# oresat-zpos-endcap.net
KiCad netlist of a schematic drawn in EAGLE
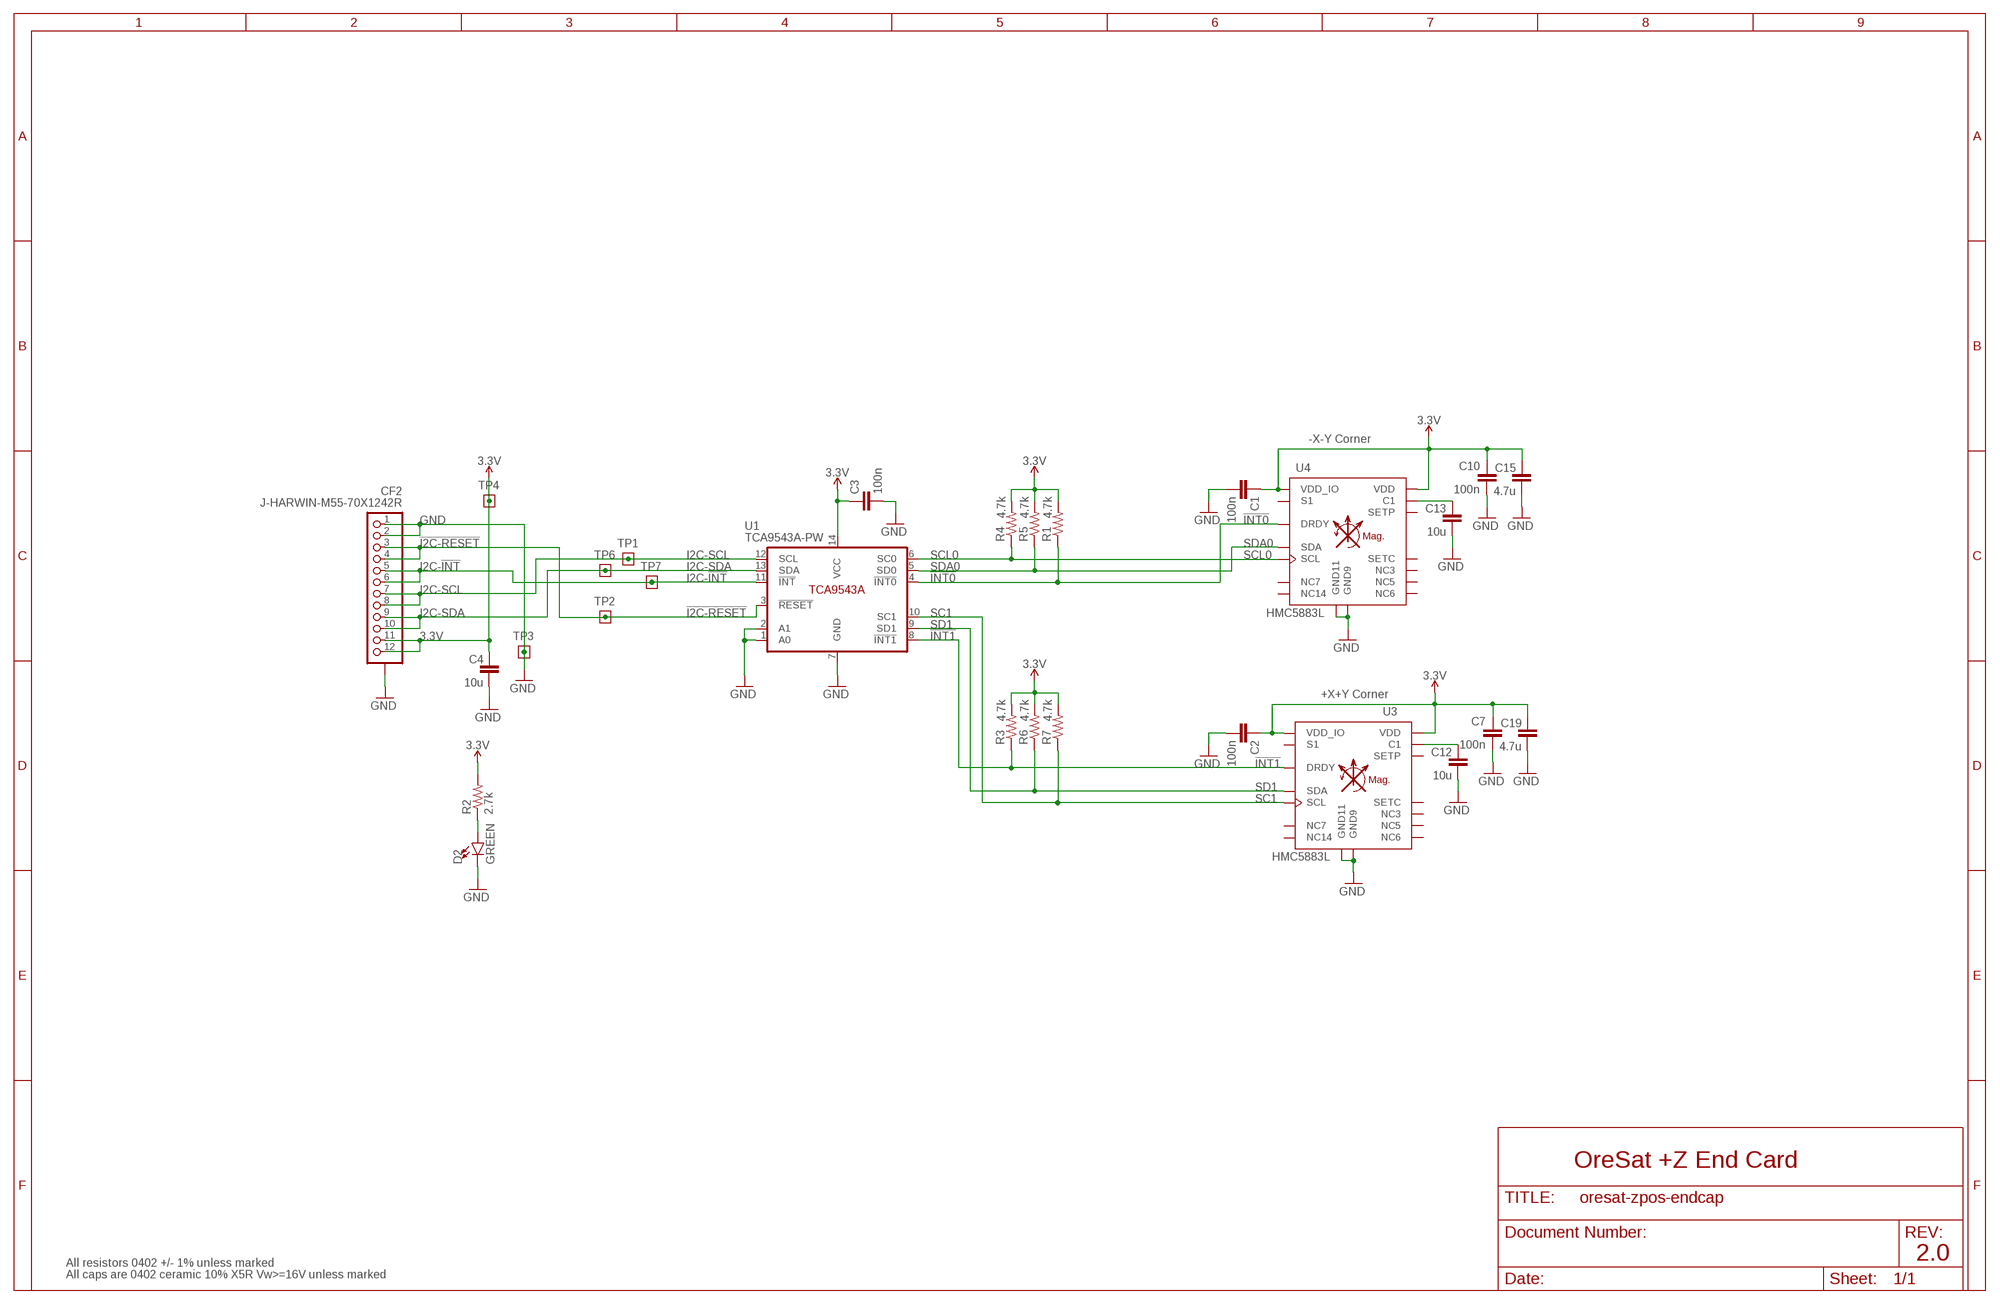
[diagram p0: schematic, sheet 1]

(export (version "E")
  (design (tool "Eeschema 10.0.6"))
  (components
    (comp (ref "C1")
      (value "100n")
      (footprint "eagle-import:.0402-B-NOSILK")
      (fields (field (name "MFR") "Samsung") (field (name "MPN") "CL05B104KO5NNNC"))
      (libsource (lib "eagle-import") (part "rcl_custom_C-EU0402-B-NOSILK"))
    )
    (comp (ref "C2")
      (value "100n")
      (footprint "eagle-import:.0402-B-NOSILK")
      (fields (field (name "MFR") "Samsung") (field (name "MPN") "CL05B104KO5NNNC"))
      (libsource (lib "eagle-import") (part "rcl_custom_C-EU0402-B-NOSILK"))
    )
    (comp (ref "C3")
      (value "100n")
      (footprint "eagle-import:.0402-B-NOSILK")
      (fields (field (name "MFR") "Samsung") (field (name "MPN") "CL05B104KO5NNNC"))
      (libsource (lib "eagle-import") (part "rcl_custom_C-EU0402-B-NOSILK"))
    )
    (comp (ref "C4")
      (value "10u")
      (footprint "eagle-import:.0603-B-NOSILK")
      (fields (field (name "MFR") "Samsung") (field (name "MPN") "CL05B104KO5NNNC"))
      (libsource (lib "eagle-import") (part "C-EU0603-B-NOSILK"))
    )
    (comp (ref "C7")
      (value "100n")
      (footprint "eagle-import:.0402-B-NOSILK")
      (fields (field (name "MFR") "Samsung") (field (name "MPN") "CL05B104KO5NNNC"))
      (libsource (lib "eagle-import") (part "rcl_custom_C-EU0402-B-NOSILK"))
    )
    (comp (ref "C10")
      (value "100n")
      (footprint "eagle-import:.0402-B-NOSILK")
      (fields (field (name "MFR") "Samsung") (field (name "MPN") "CL05B104KO5NNNC"))
      (libsource (lib "eagle-import") (part "rcl_custom_C-EU0402-B-NOSILK"))
    )
    (comp (ref "C12")
      (value "10u")
      (footprint "eagle-import:.0603-B-NOSILK")
      (fields (field (name "MFR") "Samsung") (field (name "MPN") "CL05B104KO5NNNC"))
      (libsource (lib "eagle-import") (part "C-EU0603-B-NOSILK"))
    )
    (comp (ref "C13")
      (value "10u")
      (footprint "eagle-import:.0603-B-NOSILK")
      (fields (field (name "MFR") "Samsung") (field (name "MPN") "CL05B104KO5NNNC"))
      (libsource (lib "eagle-import") (part "C-EU0603-B-NOSILK"))
    )
    (comp (ref "C15")
      (value "4.7u")
      (footprint "eagle-import:.0603-B-NOSILK")
      (fields (field (name "MFR") "Samsung") (field (name "MPN") "CL05B104KO5NNNC"))
      (libsource (lib "eagle-import") (part "C-EU0603-B-NOSILK"))
    )
    (comp (ref "C19")
      (value "4.7u")
      (footprint "eagle-import:.0603-B-NOSILK")
      (fields (field (name "MFR") "Samsung") (field (name "MPN") "CL05B104KO5NNNC"))
      (libsource (lib "eagle-import") (part "C-EU0603-B-NOSILK"))
    )
    (comp (ref "CF2")
      (value "J-HARWIN-M55-70X1242R")
      (footprint "eagle-import:HARWIN-M55-70X1242R")
      (libsource (lib "eagle-import") (part "J-HARWIN-M55-70X1242R"))
    )
    (comp (ref "D2")
      (value "GREEN")
      (footprint "eagle-import:LED-0603")
      (libsource (lib "eagle-import") (part "LED-GREEN0603"))
    )
    (comp (ref "R1")
      (value "4.7k")
      (footprint "eagle-import:.0402-B-NOSILK")
      (fields (field (name "MFR") "Samsung") (field (name "MPN") "RC1005F6653CS"))
      (libsource (lib "eagle-import") (part "R-US_0402-B-NOSILK"))
    )
    (comp (ref "R2")
      (value "2.7k")
      (footprint "eagle-import:.0402-B-NOSILK")
      (fields (field (name "MFR") "Samsung") (field (name "MPN") "RC1005F6653CS"))
      (libsource (lib "eagle-import") (part "R-US_0402-B-NOSILK"))
    )
    (comp (ref "R3")
      (value "4.7k")
      (footprint "eagle-import:.0402-B-NOSILK")
      (fields (field (name "MFR") "Samsung") (field (name "MPN") "RC1005F6653CS"))
      (libsource (lib "eagle-import") (part "R-US_0402-B-NOSILK"))
    )
    (comp (ref "R4")
      (value "4.7k")
      (footprint "eagle-import:.0402-B-NOSILK")
      (fields (field (name "MFR") "Samsung") (field (name "MPN") "RC1005F6653CS"))
      (libsource (lib "eagle-import") (part "R-US_0402-B-NOSILK"))
    )
    (comp (ref "R5")
      (value "4.7k")
      (footprint "eagle-import:.0402-B-NOSILK")
      (fields (field (name "MFR") "Samsung") (field (name "MPN") "RC1005F6653CS"))
      (libsource (lib "eagle-import") (part "R-US_0402-B-NOSILK"))
    )
    (comp (ref "R6")
      (value "4.7k")
      (footprint "eagle-import:.0402-B-NOSILK")
      (fields (field (name "MFR") "Samsung") (field (name "MPN") "RC1005F6653CS"))
      (libsource (lib "eagle-import") (part "R-US_0402-B-NOSILK"))
    )
    (comp (ref "R7")
      (value "4.7k")
      (footprint "eagle-import:.0402-B-NOSILK")
      (fields (field (name "MFR") "Samsung") (field (name "MPN") "RC1005F6653CS"))
      (libsource (lib "eagle-import") (part "R-US_0402-B-NOSILK"))
    )
    (comp (ref "TP1")
      (value "TEST-POINT")
      (footprint "eagle-import:2MM-TEST-POINT")
      (libsource (lib "eagle-import") (part "TEST-POINT"))
    )
    (comp (ref "TP2")
      (value "TEST-POINT")
      (footprint "eagle-import:2MM-TEST-POINT")
      (libsource (lib "eagle-import") (part "TEST-POINT"))
    )
    (comp (ref "TP3")
      (value "TEST-POINT")
      (footprint "eagle-import:2MM-TEST-POINT")
      (libsource (lib "eagle-import") (part "TEST-POINT"))
    )
    (comp (ref "TP4")
      (value "TEST-POINT")
      (footprint "eagle-import:2MM-TEST-POINT")
      (libsource (lib "eagle-import") (part "TEST-POINT"))
    )
    (comp (ref "TP6")
      (value "TEST-POINT")
      (footprint "eagle-import:2MM-TEST-POINT")
      (libsource (lib "eagle-import") (part "TEST-POINT"))
    )
    (comp (ref "TP7")
      (value "TEST-POINT")
      (footprint "eagle-import:2MM-TEST-POINT")
      (libsource (lib "eagle-import") (part "TEST-POINT"))
    )
    (comp (ref "U1")
      (value "TCA9543A-PW")
      (footprint "eagle-import:TSSOP14-0.65-5.4X4.4MM")
      (libsource (lib "eagle-import") (part "TCA9543A-PW"))
    )
    (comp (ref "U3")
      (value "HMC5883L")
      (footprint "eagle-import:QLGA-16(3X3)")
      (libsource (lib "eagle-import") (part "HMC5883L-LGA-16"))
    )
    (comp (ref "U4")
      (value "HMC5883L")
      (footprint "eagle-import:QLGA-16(3X3)")
      (libsource (lib "eagle-import") (part "HMC5883L-LGA-16"))
    )
  )
  (nets
    (net (code "1") (name "/I2C-SCL") (class "Default")
      (node (ref "CF2") (pin "7") (pinfunction "7_7") (pintype "passive"))
      (node (ref "CF2") (pin "8") (pinfunction "8_8") (pintype "passive"))
      (node (ref "TP1") (pin "1") (pinfunction "1_1") (pintype "passive"))
      (node (ref "U1") (pin "12") (pinfunction "SCL_12") (pintype "input"))
    )
    (net (code "2") (name "/I2C-SDA") (class "Default")
      (node (ref "CF2") (pin "10") (pinfunction "10_10") (pintype "passive"))
      (node (ref "CF2") (pin "9") (pinfunction "9_9") (pintype "passive"))
      (node (ref "TP6") (pin "1") (pinfunction "1_1") (pintype "passive"))
      (node (ref "U1") (pin "13") (pinfunction "SDA_13") (pintype "bidirectional"))
    )
    (net (code "3") (name "/I2C-~{INT}") (class "Default")
      (node (ref "CF2") (pin "5") (pinfunction "5_5") (pintype "passive"))
      (node (ref "CF2") (pin "6") (pinfunction "6_6") (pintype "passive"))
      (node (ref "TP7") (pin "1") (pinfunction "1_1") (pintype "passive"))
      (node (ref "U1") (pin "11") (pinfunction "~{INT}_11") (pintype "open_collector"))
    )
    (net (code "4") (name "/SC1") (class "Default")
      (node (ref "R7") (pin "1") (pinfunction "1_1") (pintype "passive"))
      (node (ref "U1") (pin "10") (pinfunction "SC1_10") (pintype "output"))
      (node (ref "U3") (pin "1") (pinfunction "SCL_1") (pintype "input"))
    )
    (net (code "5") (name "/SCL0") (class "Default")
      (node (ref "R4") (pin "1") (pinfunction "1_1") (pintype "passive"))
      (node (ref "U1") (pin "6") (pinfunction "SC0_6") (pintype "output"))
      (node (ref "U4") (pin "1") (pinfunction "SCL_1") (pintype "input"))
    )
    (net (code "6") (name "/SD1") (class "Default")
      (node (ref "R6") (pin "1") (pinfunction "1_1") (pintype "passive"))
      (node (ref "U1") (pin "9") (pinfunction "SD1_9") (pintype "bidirectional"))
      (node (ref "U3") (pin "16") (pinfunction "SDA_16") (pintype "bidirectional"))
    )
    (net (code "7") (name "/SDA0") (class "Default")
      (node (ref "R5") (pin "1") (pinfunction "1_1") (pintype "passive"))
      (node (ref "U1") (pin "5") (pinfunction "SD0_5") (pintype "bidirectional"))
      (node (ref "U4") (pin "16") (pinfunction "SDA_16") (pintype "bidirectional"))
    )
    (net (code "8") (name "/~{I2C-RESET}") (class "Default")
      (node (ref "CF2") (pin "3") (pinfunction "3_3") (pintype "passive"))
      (node (ref "CF2") (pin "4") (pinfunction "4_4") (pintype "passive"))
      (node (ref "TP2") (pin "1") (pinfunction "1_1") (pintype "passive"))
      (node (ref "U1") (pin "3") (pinfunction "~{RESET}_3") (pintype "input"))
    )
    (net (code "9") (name "/~{INT0}") (class "Default")
      (node (ref "R1") (pin "1") (pinfunction "1_1") (pintype "passive"))
      (node (ref "U1") (pin "4") (pinfunction "~{INT0}_4") (pintype "input"))
      (node (ref "U4") (pin "15") (pinfunction "DRDY_15") (pintype "output"))
    )
    (net (code "10") (name "/~{INT1}") (class "Default")
      (node (ref "R3") (pin "1") (pinfunction "1_1") (pintype "passive"))
      (node (ref "U1") (pin "8") (pinfunction "~{INT1}_8") (pintype "input"))
      (node (ref "U3") (pin "15") (pinfunction "DRDY_15") (pintype "output"))
    )
    (net (code "11") (name "3.3V") (class "Default")
      (node (ref "C1") (pin "1") (pinfunction "1_1") (pintype "passive"))
      (node (ref "C10") (pin "1") (pinfunction "1_1") (pintype "passive"))
      (node (ref "C15") (pin "1") (pinfunction "1_1") (pintype "passive"))
      (node (ref "C19") (pin "1") (pinfunction "1_1") (pintype "passive"))
      (node (ref "C2") (pin "1") (pinfunction "1_1") (pintype "passive"))
      (node (ref "C3") (pin "1") (pinfunction "1_1") (pintype "passive"))
      (node (ref "C4") (pin "1") (pinfunction "1_1") (pintype "passive"))
      (node (ref "C7") (pin "1") (pinfunction "1_1") (pintype "passive"))
      (node (ref "CF2") (pin "11") (pinfunction "11_11") (pintype "passive"))
      (node (ref "CF2") (pin "12") (pinfunction "12_12") (pintype "passive"))
      (node (ref "R1") (pin "2") (pinfunction "2_2") (pintype "passive"))
      (node (ref "R2") (pin "2") (pinfunction "2_2") (pintype "passive"))
      (node (ref "R3") (pin "2") (pinfunction "2_2") (pintype "passive"))
      (node (ref "R4") (pin "2") (pinfunction "2_2") (pintype "passive"))
      (node (ref "R5") (pin "2") (pinfunction "2_2") (pintype "passive"))
      (node (ref "R6") (pin "2") (pinfunction "2_2") (pintype "passive"))
      (node (ref "R7") (pin "2") (pinfunction "2_2") (pintype "passive"))
      (node (ref "TP4") (pin "1") (pinfunction "1_1") (pintype "passive"))
      (node (ref "U1") (pin "14") (pinfunction "VCC_14") (pintype "power_in"))
      (node (ref "U3") (pin "13") (pinfunction "VDD_IO_13") (pintype "power_in"))
      (node (ref "U3") (pin "2") (pinfunction "VDD_2") (pintype "power_in"))
      (node (ref "U4") (pin "13") (pinfunction "VDD_IO_13") (pintype "power_in"))
      (node (ref "U4") (pin "2") (pinfunction "VDD_2") (pintype "power_in"))
    )
    (net (code "12") (name "GND") (class "Default")
      (node (ref "C1") (pin "2") (pinfunction "2_2") (pintype "passive"))
      (node (ref "C10") (pin "2") (pinfunction "2_2") (pintype "passive"))
      (node (ref "C12") (pin "2") (pinfunction "2_2") (pintype "passive"))
      (node (ref "C13") (pin "2") (pinfunction "2_2") (pintype "passive"))
      (node (ref "C15") (pin "2") (pinfunction "2_2") (pintype "passive"))
      (node (ref "C19") (pin "2") (pinfunction "2_2") (pintype "passive"))
      (node (ref "C2") (pin "2") (pinfunction "2_2") (pintype "passive"))
      (node (ref "C3") (pin "2") (pinfunction "2_2") (pintype "passive"))
      (node (ref "C4") (pin "2") (pinfunction "2_2") (pintype "passive"))
      (node (ref "C7") (pin "2") (pinfunction "2_2") (pintype "passive"))
      (node (ref "CF2") (pin "1") (pinfunction "1_1") (pintype "passive"))
      (node (ref "CF2") (pin "2") (pinfunction "2_2") (pintype "passive"))
      (node (ref "CF2") (pin "P$1") (pinfunction "SHIELDS_P$1") (pintype "passive"))
      (node (ref "CF2") (pin "P$2") (pinfunction "SHIELDS_P$2") (pintype "passive"))
      (node (ref "CF2") (pin "P$3") (pinfunction "SHIELDS_P$3") (pintype "passive"))
      (node (ref "CF2") (pin "P$4") (pinfunction "SHIELDS_P$4") (pintype "passive"))
      (node (ref "D2") (pin "C") (pinfunction "C_C") (pintype "passive"))
      (node (ref "TP3") (pin "1") (pinfunction "1_1") (pintype "passive"))
      (node (ref "U1") (pin "1") (pinfunction "A0_1") (pintype "input"))
      (node (ref "U1") (pin "2") (pinfunction "A1_2") (pintype "input"))
      (node (ref "U1") (pin "7") (pinfunction "GND_7") (pintype "power_in"))
      (node (ref "U3") (pin "11") (pinfunction "GND11_11") (pintype "power_in"))
      (node (ref "U3") (pin "9") (pinfunction "GND9_9") (pintype "power_in"))
      (node (ref "U4") (pin "11") (pinfunction "GND11_11") (pintype "power_in"))
      (node (ref "U4") (pin "9") (pinfunction "GND9_9") (pintype "power_in"))
    )
    (net (code "13") (name "Net-(D2-PadA)") (class "Default")
      (node (ref "D2") (pin "A") (pinfunction "A_A") (pintype "passive"))
      (node (ref "R2") (pin "1") (pinfunction "1_1") (pintype "passive"))
    )
    (net (code "14") (name "Net-(U3-C1)") (class "Default")
      (node (ref "C12") (pin "1") (pinfunction "1_1") (pintype "passive"))
      (node (ref "U3") (pin "10") (pinfunction "C1_10") (pintype "passive"))
    )
    (net (code "15") (name "Net-(U4-C1)") (class "Default")
      (node (ref "C13") (pin "1") (pinfunction "1_1") (pintype "passive"))
      (node (ref "U4") (pin "10") (pinfunction "C1_10") (pintype "passive"))
    )
    (net (code "16") (name "unconnected-(U3-NC3-Pad3)") (class "Default")
      (node (ref "U3") (pin "3") (pinfunction "NC3_3") (pintype "no_connect"))
    )
    (net (code "17") (name "unconnected-(U3-NC5-Pad5)") (class "Default")
      (node (ref "U3") (pin "5") (pinfunction "NC5_5") (pintype "no_connect"))
    )
    (net (code "18") (name "unconnected-(U3-NC6-Pad6)") (class "Default")
      (node (ref "U3") (pin "6") (pinfunction "NC6_6") (pintype "no_connect"))
    )
    (net (code "19") (name "unconnected-(U3-NC7-Pad7)") (class "Default")
      (node (ref "U3") (pin "7") (pinfunction "NC7_7") (pintype "no_connect"))
    )
    (net (code "20") (name "unconnected-(U3-NC14-Pad14)") (class "Default")
      (node (ref "U3") (pin "14") (pinfunction "NC14_14") (pintype "no_connect"))
    )
    (net (code "21") (name "unconnected-(U3-S1-Pad4)") (class "Default")
      (node (ref "U3") (pin "4") (pinfunction "S1_4") (pintype "input"))
    )
    (net (code "22") (name "unconnected-(U3-SETC-Pad12)") (class "Default")
      (node (ref "U3") (pin "12") (pinfunction "SETC_12") (pintype "output"))
    )
    (net (code "23") (name "unconnected-(U3-SETP-Pad8)") (class "Default")
      (node (ref "U3") (pin "8") (pinfunction "SETP_8") (pintype "passive"))
    )
    (net (code "24") (name "unconnected-(U4-NC3-Pad3)") (class "Default")
      (node (ref "U4") (pin "3") (pinfunction "NC3_3") (pintype "no_connect"))
    )
    (net (code "25") (name "unconnected-(U4-NC5-Pad5)") (class "Default")
      (node (ref "U4") (pin "5") (pinfunction "NC5_5") (pintype "no_connect"))
    )
    (net (code "26") (name "unconnected-(U4-NC6-Pad6)") (class "Default")
      (node (ref "U4") (pin "6") (pinfunction "NC6_6") (pintype "no_connect"))
    )
    (net (code "27") (name "unconnected-(U4-NC7-Pad7)") (class "Default")
      (node (ref "U4") (pin "7") (pinfunction "NC7_7") (pintype "no_connect"))
    )
    (net (code "28") (name "unconnected-(U4-NC14-Pad14)") (class "Default")
      (node (ref "U4") (pin "14") (pinfunction "NC14_14") (pintype "no_connect"))
    )
    (net (code "29") (name "unconnected-(U4-S1-Pad4)") (class "Default")
      (node (ref "U4") (pin "4") (pinfunction "S1_4") (pintype "input"))
    )
    (net (code "30") (name "unconnected-(U4-SETC-Pad12)") (class "Default")
      (node (ref "U4") (pin "12") (pinfunction "SETC_12") (pintype "output"))
    )
    (net (code "31") (name "unconnected-(U4-SETP-Pad8)") (class "Default")
      (node (ref "U4") (pin "8") (pinfunction "SETP_8") (pintype "passive"))
    )
  )
)
